# CPU_eMMC_TF.net
KiCad netlist of a schematic drawn in Altium Designer
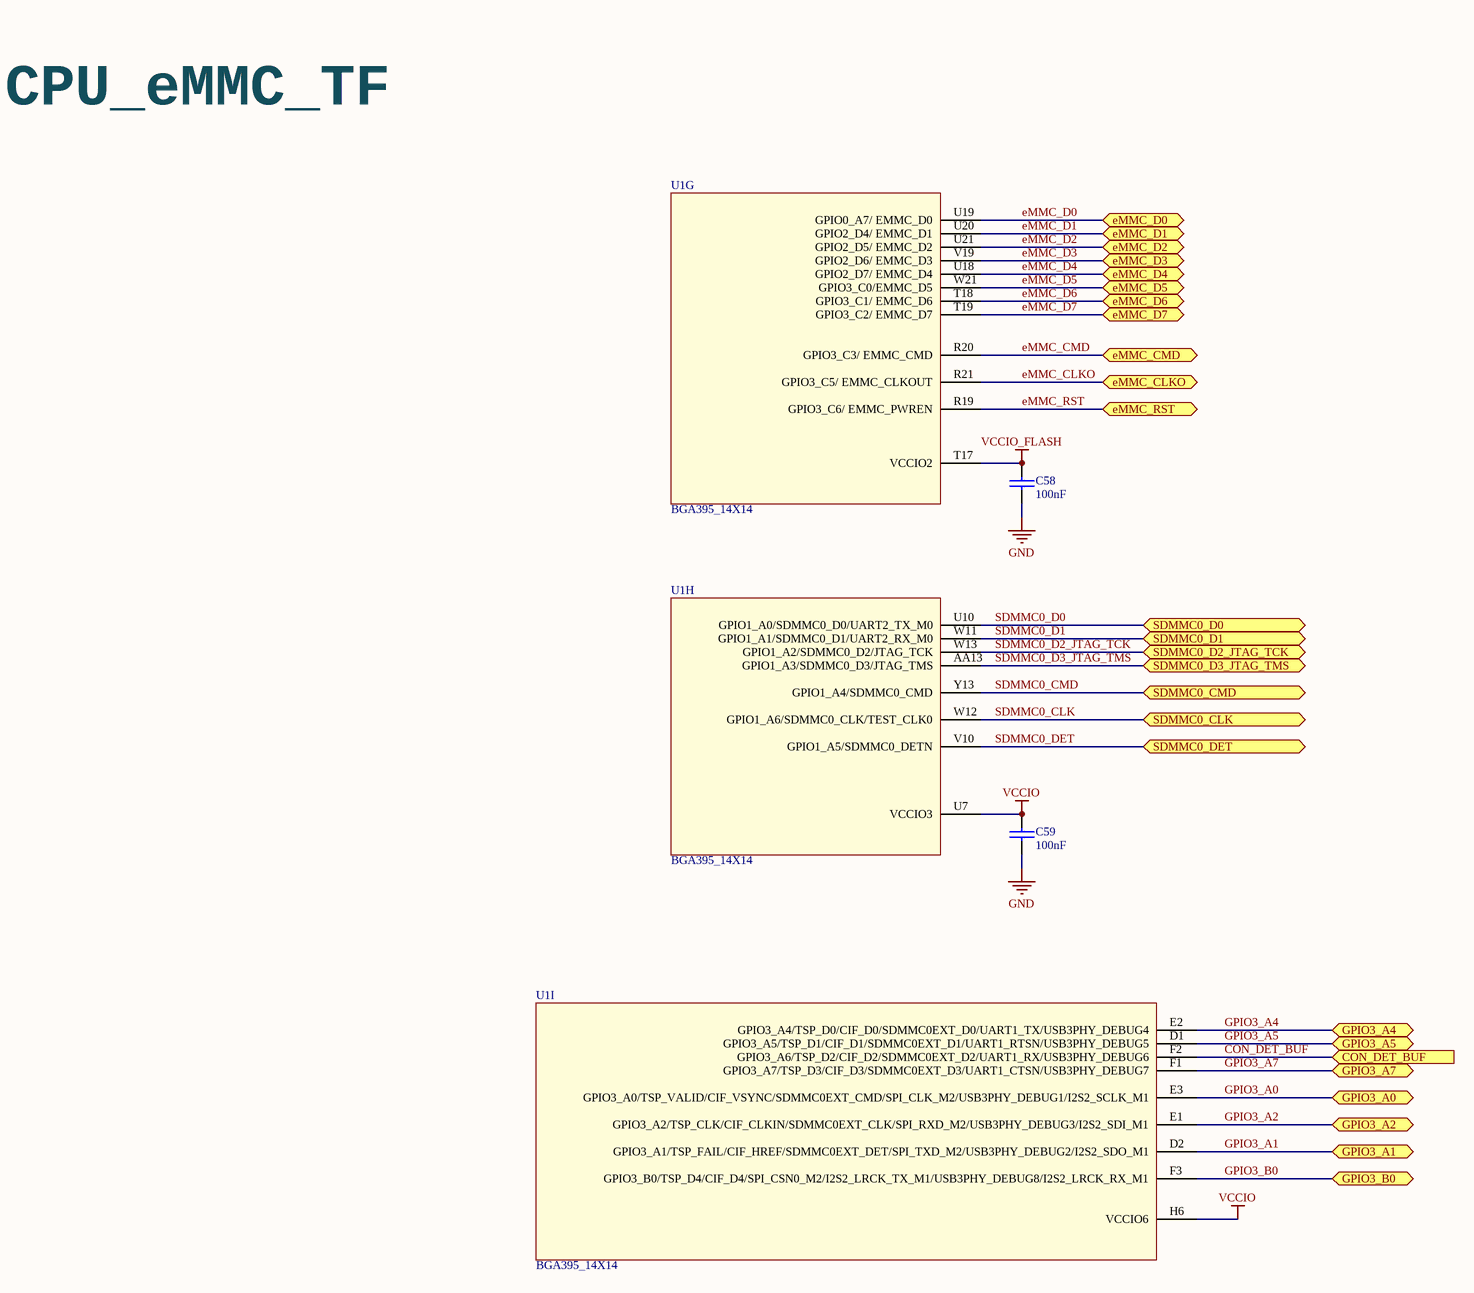
[diagram p0: CPU_eMMC_TF.SchDoc]

(export (version "E")
  (design (tool "Eeschema 10.0.6"))
  (components
    (comp (ref "C58")
      (value "100nF")
      (footprint "0402_CC - C")
      (libsource (lib "AAR_RockChip_RK3328") (part "CAP_NP"))
    )
    (comp (ref "C59")
      (value "100nF")
      (footprint "0402_CC - C")
      (libsource (lib "AAR_RockChip_RK3328") (part "CAP_NP"))
    )
    (comp (ref "U1")
      (value "BGA395_14X14")
      (footprint "BGA395C65P21X21_1750X1750X117")
      (description "By AAR")
      (libsource (lib "AAR_RockChip_RK3328") (part "RK3328"))
    )
  )
  (nets
    (net (code "1") (name "/CON_DET_BUF") (class "Default")
      (node (ref "U1") (pin "F2") (pinfunction "GPIO3_A6/TSP_D2/CIF_D2/SDMMC0EXT_D2/UART1_RX/USB3PHY_DEBUG6_F2") (pintype "passive"))
    )
    (net (code "2") (name "/GPIO3_A0") (class "Default")
      (node (ref "U1") (pin "E3") (pinfunction "GPIO3_A0/TSP_VALID/CIF_VSYNC/SDMMC0EXT_CMD/SPI_CLK_M2/USB3PHY_DEBUG1/I2S2_SCLK_M1_E3") (pintype "passive"))
    )
    (net (code "3") (name "/GPIO3_A1") (class "Default")
      (node (ref "U1") (pin "D2") (pinfunction "GPIO3_A1/TSP_FAIL/CIF_HREF/SDMMC0EXT_DET/SPI_TXD_M2/USB3PHY_DEBUG2/I2S2_SDO_M1_D2") (pintype "passive"))
    )
    (net (code "4") (name "/GPIO3_A2") (class "Default")
      (node (ref "U1") (pin "E1") (pinfunction "GPIO3_A2/TSP_CLK/CIF_CLKIN/SDMMC0EXT_CLK/SPI_RXD_M2/USB3PHY_DEBUG3/I2S2_SDI_M1_E1") (pintype "passive"))
    )
    (net (code "5") (name "/GPIO3_A4") (class "Default")
      (node (ref "U1") (pin "E2") (pinfunction "GPIO3_A4/TSP_D0/CIF_D0/SDMMC0EXT_D0/UART1_TX/USB3PHY_DEBUG4_E2") (pintype "passive"))
    )
    (net (code "6") (name "/GPIO3_A5") (class "Default")
      (node (ref "U1") (pin "D1") (pinfunction "GPIO3_A5/TSP_D1/CIF_D1/SDMMC0EXT_D1/UART1_RTSN/USB3PHY_DEBUG5_D1") (pintype "passive"))
    )
    (net (code "7") (name "/GPIO3_A7") (class "Default")
      (node (ref "U1") (pin "F1") (pinfunction "GPIO3_A7/TSP_D3/CIF_D3/SDMMC0EXT_D3/UART1_CTSN/USB3PHY_DEBUG7_F1") (pintype "passive"))
    )
    (net (code "8") (name "/GPIO3_B0") (class "Default")
      (node (ref "U1") (pin "F3") (pinfunction "GPIO3_B0/TSP_D4/CIF_D4/SPI_CSN0_M2/I2S2_LRCK_TX_M1/USB3PHY_DEBUG8/I2S2_LRCK_RX_M1_F3") (pintype "passive"))
    )
    (net (code "9") (name "/SDMMC0_CLK") (class "Default")
      (node (ref "U1") (pin "W12") (pinfunction "GPIO1_A6/SDMMC0_CLK/TEST_CLK0_W12") (pintype "passive"))
    )
    (net (code "10") (name "/SDMMC0_CMD") (class "Default")
      (node (ref "U1") (pin "Y13") (pinfunction "GPIO1_A4/SDMMC0_CMD_Y13") (pintype "passive"))
    )
    (net (code "11") (name "/SDMMC0_D0") (class "Default")
      (node (ref "U1") (pin "U10") (pinfunction "GPIO1_A0/SDMMC0_D0/UART2_TX_M0_U10") (pintype "passive"))
    )
    (net (code "12") (name "/SDMMC0_D1") (class "Default")
      (node (ref "U1") (pin "W11") (pinfunction "GPIO1_A1/SDMMC0_D1/UART2_RX_M0_W11") (pintype "passive"))
    )
    (net (code "13") (name "/SDMMC0_D2_JTAG_TCK") (class "Default")
      (node (ref "U1") (pin "W13") (pinfunction "GPIO1_A2/SDMMC0_D2/JTAG_TCK_W13") (pintype "passive"))
    )
    (net (code "14") (name "/SDMMC0_D3_JTAG_TMS") (class "Default")
      (node (ref "U1") (pin "AA13") (pinfunction "GPIO1_A3/SDMMC0_D3/JTAG_TMS_AA13") (pintype "passive"))
    )
    (net (code "15") (name "/SDMMC0_DET") (class "Default")
      (node (ref "U1") (pin "V10") (pinfunction "GPIO1_A5/SDMMC0_DETN_V10") (pintype "passive"))
    )
    (net (code "16") (name "/eMMC_CLKO") (class "Default")
      (node (ref "U1") (pin "R21") (pinfunction "GPIO3_C5/_EMMC_CLKOUT_R21") (pintype "passive"))
    )
    (net (code "17") (name "/eMMC_CMD") (class "Default")
      (node (ref "U1") (pin "R20") (pinfunction "GPIO3_C3/_EMMC_CMD_R20") (pintype "passive"))
    )
    (net (code "18") (name "/eMMC_D0") (class "Default")
      (node (ref "U1") (pin "U19") (pinfunction "GPIO0_A7/_EMMC_D0_U19") (pintype "passive"))
    )
    (net (code "19") (name "/eMMC_D1") (class "Default")
      (node (ref "U1") (pin "U20") (pinfunction "GPIO2_D4/_EMMC_D1_U20") (pintype "passive"))
    )
    (net (code "20") (name "/eMMC_D2") (class "Default")
      (node (ref "U1") (pin "U21") (pinfunction "GPIO2_D5/_EMMC_D2_U21") (pintype "passive"))
    )
    (net (code "21") (name "/eMMC_D3") (class "Default")
      (node (ref "U1") (pin "V19") (pinfunction "GPIO2_D6/_EMMC_D3_V19") (pintype "passive"))
    )
    (net (code "22") (name "/eMMC_D4") (class "Default")
      (node (ref "U1") (pin "U18") (pinfunction "GPIO2_D7/_EMMC_D4_U18") (pintype "passive"))
    )
    (net (code "23") (name "/eMMC_D5") (class "Default")
      (node (ref "U1") (pin "W21") (pinfunction "GPIO3_C0/EMMC_D5_W21") (pintype "passive"))
    )
    (net (code "24") (name "/eMMC_D6") (class "Default")
      (node (ref "U1") (pin "T18") (pinfunction "GPIO3_C1/_EMMC_D6_T18") (pintype "passive"))
    )
    (net (code "25") (name "/eMMC_D7") (class "Default")
      (node (ref "U1") (pin "T19") (pinfunction "GPIO3_C2/_EMMC_D7_T19") (pintype "passive"))
    )
    (net (code "26") (name "/eMMC_RST") (class "Default")
      (node (ref "U1") (pin "R19") (pinfunction "GPIO3_C6/_EMMC_PWREN_R19") (pintype "passive"))
    )
    (net (code "27") (name "GND") (class "Default")
      (node (ref "C58") (pin "2") (pinfunction "2_2") (pintype "passive"))
      (node (ref "C59") (pin "2") (pinfunction "2_2") (pintype "passive"))
    )
    (net (code "28") (name "VCCIO") (class "Default")
      (node (ref "C59") (pin "1") (pinfunction "1_1") (pintype "passive"))
      (node (ref "U1") (pin "H6") (pinfunction "VCCIO6_H6") (pintype "passive"))
      (node (ref "U1") (pin "U7") (pinfunction "VCCIO3_U7") (pintype "passive"))
    )
    (net (code "29") (name "VCCIO_FLASH") (class "Default")
      (node (ref "C58") (pin "1") (pinfunction "1_1") (pintype "passive"))
      (node (ref "U1") (pin "T17") (pinfunction "VCCIO2_T17") (pintype "passive"))
    )
  )
)
